# rat17-18.net
KiCad netlist of a schematic drawn in EAGLE
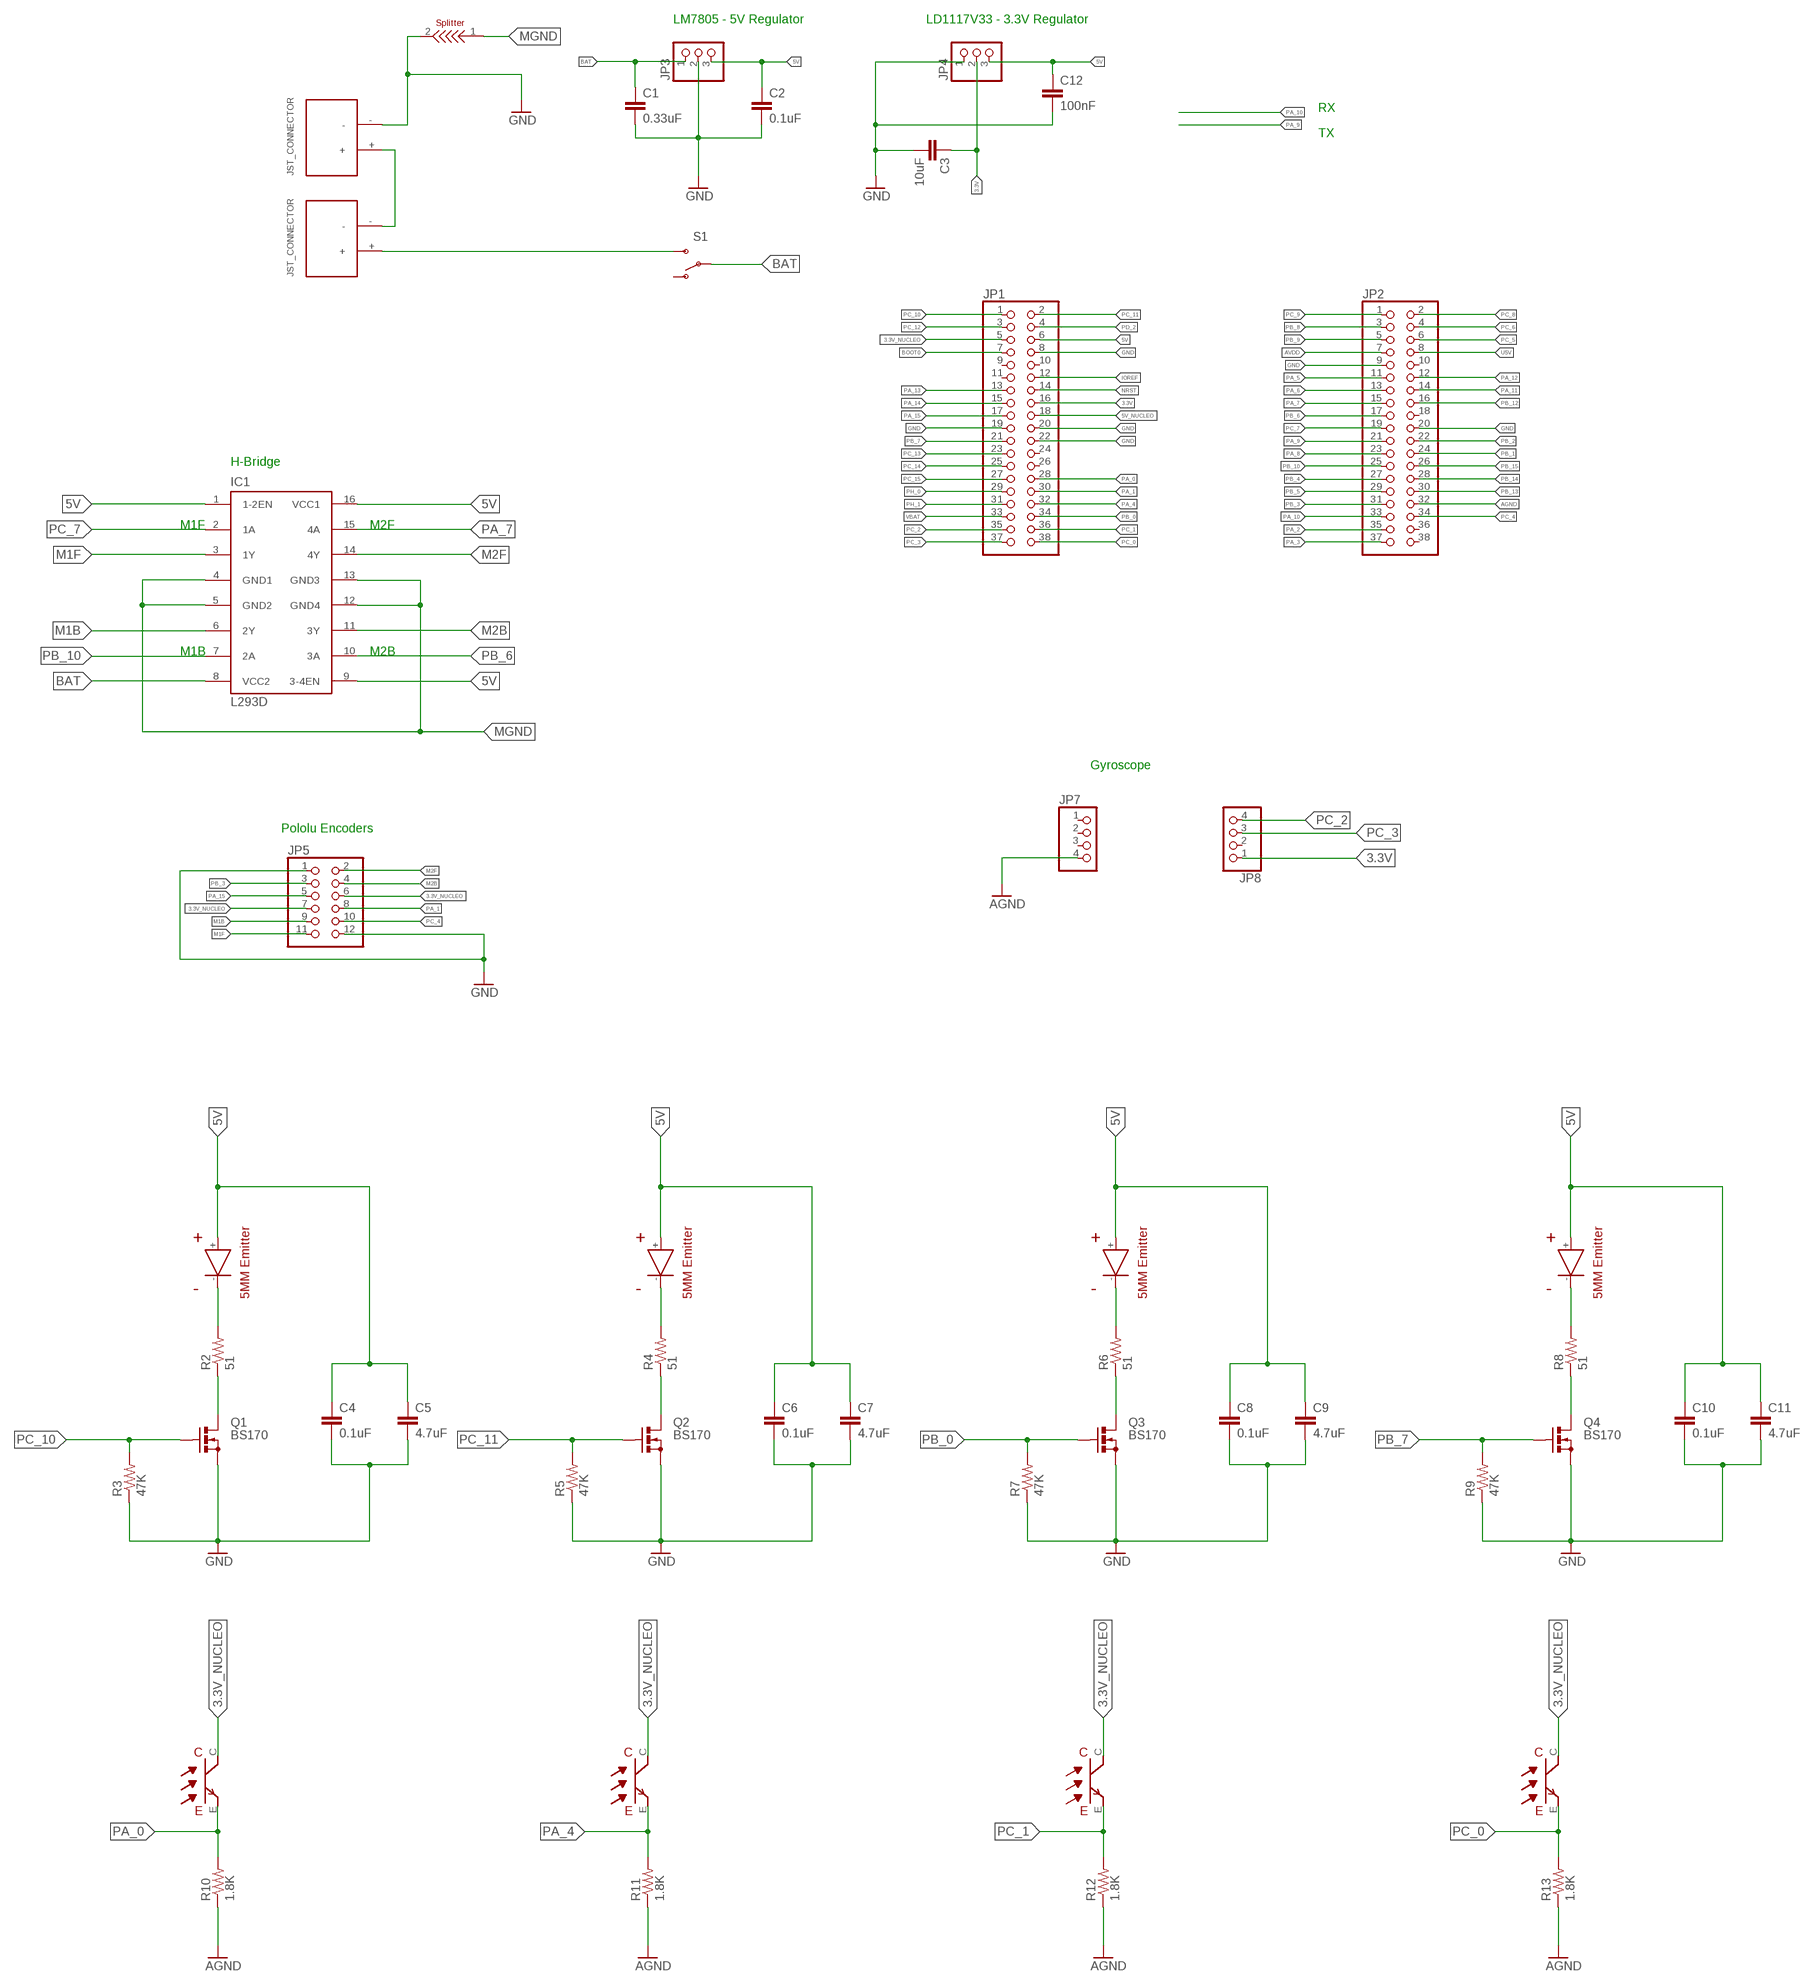
[diagram p0: schematic, sheet 1]

(export (version "E")
  (design (tool "Eeschema 10.0.6"))
  (components
    (comp (ref "C1")
      (value "0.33uF")
      (footprint "eagle-import:AXIAL-5MM")
      (libsource (lib "eagle-import") (part "CAP_"))
    )
    (comp (ref "C2")
      (value "0.1uF")
      (footprint "eagle-import:AXIAL-5MM")
      (libsource (lib "eagle-import") (part "CAP_"))
    )
    (comp (ref "C3")
      (value "10uF")
      (footprint "eagle-import:AXIAL-5MM")
      (libsource (lib "eagle-import") (part "CAP_"))
    )
    (comp (ref "C4")
      (value "0.1uF")
      (footprint "eagle-import:AXIAL-5MM")
      (libsource (lib "eagle-import") (part "CAP_"))
    )
    (comp (ref "C5")
      (value "4.7uF")
      (footprint "eagle-import:AXIAL-5MM")
      (libsource (lib "eagle-import") (part "CAP_"))
    )
    (comp (ref "C6")
      (value "0.1uF")
      (footprint "eagle-import:AXIAL-5MM")
      (libsource (lib "eagle-import") (part "CAP_"))
    )
    (comp (ref "C7")
      (value "4.7uF")
      (footprint "eagle-import:AXIAL-5MM")
      (libsource (lib "eagle-import") (part "CAP_"))
    )
    (comp (ref "C8")
      (value "0.1uF")
      (footprint "eagle-import:AXIAL-5MM")
      (libsource (lib "eagle-import") (part "CAP_"))
    )
    (comp (ref "C9")
      (value "4.7uF")
      (footprint "eagle-import:AXIAL-5MM")
      (libsource (lib "eagle-import") (part "CAP_"))
    )
    (comp (ref "C10")
      (value "0.1uF")
      (footprint "eagle-import:AXIAL-5MM")
      (libsource (lib "eagle-import") (part "CAP_"))
    )
    (comp (ref "C11")
      (value "4.7uF")
      (footprint "eagle-import:AXIAL-5MM")
      (libsource (lib "eagle-import") (part "CAP_"))
    )
    (comp (ref "C12")
      (value "100nF")
      (footprint "eagle-import:AXIAL-5MM")
      (libsource (lib "eagle-import") (part "CAP_"))
    )
    (comp (ref "IC1")
      (value "L293D")
      (footprint "eagle-import:DIL16")
      (libsource (lib "eagle-import") (part "L293D"))
    )
    (comp (ref "JP1")
      (value "PINHD-2X19")
      (footprint "eagle-import:2X19")
      (libsource (lib "eagle-import") (part "PINHD-2X19"))
    )
    (comp (ref "JP2")
      (value "PINHD-2X19")
      (footprint "eagle-import:2X19")
      (libsource (lib "eagle-import") (part "PINHD-2X19"))
    )
    (comp (ref "JP3")
      (value "PINHD-1X3")
      (footprint "eagle-import:1X03")
      (libsource (lib "eagle-import") (part "PINHD-1X3"))
    )
    (comp (ref "JP4")
      (value "PINHD-1X3")
      (footprint "eagle-import:1X03")
      (libsource (lib "eagle-import") (part "PINHD-1X3"))
    )
    (comp (ref "JP5")
      (value "PINHD-2X6")
      (footprint "eagle-import:2X06")
      (libsource (lib "eagle-import") (part "PINHD-2X6"))
    )
    (comp (ref "JP7")
      (value "PINHD-1X4")
      (footprint "eagle-import:1X04")
      (libsource (lib "eagle-import") (part "PINHD-1X4"))
    )
    (comp (ref "JP8")
      (value "PINHD-1X4")
      (footprint "eagle-import:1X04")
      (libsource (lib "eagle-import") (part "PINHD-1X4"))
    )
    (comp (ref "Q1")
      (value "BS170")
      (footprint "eagle-import:SOT54E")
      (libsource (lib "eagle-import") (part "BS170"))
    )
    (comp (ref "Q2")
      (value "BS170")
      (footprint "eagle-import:SOT54E")
      (libsource (lib "eagle-import") (part "BS170"))
    )
    (comp (ref "Q3")
      (value "BS170")
      (footprint "eagle-import:SOT54E")
      (libsource (lib "eagle-import") (part "BS170"))
    )
    (comp (ref "Q4")
      (value "BS170")
      (footprint "eagle-import:SOT54E")
      (libsource (lib "eagle-import") (part "BS170"))
    )
    (comp (ref "R2")
      (value "51")
      (footprint "eagle-import:AXIAL-0.3")
      (libsource (lib "eagle-import") (part "RESISTORAXIAL-0.3"))
    )
    (comp (ref "R3")
      (value "47K")
      (footprint "eagle-import:AXIAL-0.3")
      (libsource (lib "eagle-import") (part "RESISTORAXIAL-0.3"))
    )
    (comp (ref "R4")
      (value "51")
      (footprint "eagle-import:AXIAL-0.3")
      (libsource (lib "eagle-import") (part "RESISTORAXIAL-0.3"))
    )
    (comp (ref "R5")
      (value "47K")
      (footprint "eagle-import:AXIAL-0.3")
      (libsource (lib "eagle-import") (part "RESISTORAXIAL-0.3"))
    )
    (comp (ref "R6")
      (value "51")
      (footprint "eagle-import:AXIAL-0.3")
      (libsource (lib "eagle-import") (part "RESISTORAXIAL-0.3"))
    )
    (comp (ref "R7")
      (value "47K")
      (footprint "eagle-import:AXIAL-0.3")
      (libsource (lib "eagle-import") (part "RESISTORAXIAL-0.3"))
    )
    (comp (ref "R8")
      (value "51")
      (footprint "eagle-import:AXIAL-0.3")
      (libsource (lib "eagle-import") (part "RESISTORAXIAL-0.3"))
    )
    (comp (ref "R9")
      (value "47K")
      (footprint "eagle-import:AXIAL-0.3")
      (libsource (lib "eagle-import") (part "RESISTORAXIAL-0.3"))
    )
    (comp (ref "R10")
      (value "1.8K")
      (footprint "eagle-import:AXIAL-0.3")
      (libsource (lib "eagle-import") (part "RESISTORAXIAL-0.3"))
    )
    (comp (ref "R11")
      (value "1.8K")
      (footprint "eagle-import:AXIAL-0.3")
      (libsource (lib "eagle-import") (part "RESISTORAXIAL-0.3"))
    )
    (comp (ref "R12")
      (value "1.8K")
      (footprint "eagle-import:AXIAL-0.3")
      (libsource (lib "eagle-import") (part "RESISTORAXIAL-0.3"))
    )
    (comp (ref "R13")
      (value "1.8K")
      (footprint "eagle-import:AXIAL-0.3")
      (libsource (lib "eagle-import") (part "RESISTORAXIAL-0.3"))
    )
    (comp (ref "S1")
      (value "SWITCH-SPSTPTH")
      (footprint "eagle-import:SWITCH-SPDT")
      (libsource (lib "eagle-import") (part "SWITCH-SPSTPTH"))
    )
    (comp (ref "U$1")
      (value "JST_CONNECTOR_FEMALE")
      (footprint "eagle-import:JST_CONNECTOR_FEMALE")
      (libsource (lib "eagle-import") (part "JST_CONNECTOR_FEMALE"))
    )
    (comp (ref "U$2")
      (value "JST_CONNECTOR_FEMALE")
      (footprint "eagle-import:JST_CONNECTOR_FEMALE")
      (libsource (lib "eagle-import") (part "JST_CONNECTOR_FEMALE"))
    )
    (comp (ref "U$3")
      (value "SPLITTER")
      (footprint "eagle-import:SPLITTER")
      (libsource (lib "eagle-import") (part "SPLITTER"))
    )
    (comp (ref "U$4")
      (value "RECEIVER")
      (footprint "eagle-import:RECEIVER")
      (libsource (lib "eagle-import") (part "RECEIVER"))
    )
    (comp (ref "U$5")
      (value "EMITTER")
      (footprint "eagle-import:EMITTER")
      (libsource (lib "eagle-import") (part "EMITTER"))
    )
    (comp (ref "U$6")
      (value "EMITTER")
      (footprint "eagle-import:EMITTER")
      (libsource (lib "eagle-import") (part "EMITTER"))
    )
    (comp (ref "U$7")
      (value "EMITTER")
      (footprint "eagle-import:EMITTER")
      (libsource (lib "eagle-import") (part "EMITTER"))
    )
    (comp (ref "U$8")
      (value "EMITTER")
      (footprint "eagle-import:EMITTER")
      (libsource (lib "eagle-import") (part "EMITTER"))
    )
    (comp (ref "U$15")
      (value "RECEIVER")
      (footprint "eagle-import:RECEIVER")
      (libsource (lib "eagle-import") (part "RECEIVER"))
    )
    (comp (ref "U$18")
      (value "RECEIVER")
      (footprint "eagle-import:RECEIVER")
      (libsource (lib "eagle-import") (part "RECEIVER"))
    )
    (comp (ref "U$19")
      (value "RECEIVER")
      (footprint "eagle-import:RECEIVER")
      (libsource (lib "eagle-import") (part "RECEIVER"))
    )
  )
  (nets
    (net (code "1") (name "3.3V") (class "Default")
      (node (ref "C3") (pin "P$1") (pinfunction "1_P$1") (pintype "passive"))
      (node (ref "JP1") (pin "16") (pinfunction "16_16") (pintype "passive"))
      (node (ref "JP4") (pin "2") (pinfunction "2_2") (pintype "passive"))
      (node (ref "JP8") (pin "1") (pinfunction "1_1") (pintype "passive"))
    )
    (net (code "2") (name "3.3V_NUCLEO") (class "Default")
      (node (ref "JP1") (pin "5") (pinfunction "5_5") (pintype "passive"))
      (node (ref "JP5") (pin "6") (pinfunction "6_6") (pintype "passive"))
      (node (ref "JP5") (pin "7") (pinfunction "7_7") (pintype "passive"))
      (node (ref "U$15") (pin "C") (pinfunction "C_C") (pintype "bidirectional"))
      (node (ref "U$18") (pin "C") (pinfunction "C_C") (pintype "bidirectional"))
      (node (ref "U$19") (pin "C") (pinfunction "C_C") (pintype "bidirectional"))
      (node (ref "U$4") (pin "C") (pinfunction "C_C") (pintype "bidirectional"))
    )
    (net (code "3") (name "5V") (class "Default")
      (node (ref "C10") (pin "P$1") (pinfunction "1_P$1") (pintype "passive"))
      (node (ref "C11") (pin "P$1") (pinfunction "1_P$1") (pintype "passive"))
      (node (ref "C12") (pin "P$1") (pinfunction "1_P$1") (pintype "passive"))
      (node (ref "C2") (pin "P$1") (pinfunction "1_P$1") (pintype "passive"))
      (node (ref "C4") (pin "P$1") (pinfunction "1_P$1") (pintype "passive"))
      (node (ref "C5") (pin "P$1") (pinfunction "1_P$1") (pintype "passive"))
      (node (ref "C6") (pin "P$1") (pinfunction "1_P$1") (pintype "passive"))
      (node (ref "C7") (pin "P$1") (pinfunction "1_P$1") (pintype "passive"))
      (node (ref "C8") (pin "P$1") (pinfunction "1_P$1") (pintype "passive"))
      (node (ref "C9") (pin "P$1") (pinfunction "1_P$1") (pintype "passive"))
      (node (ref "IC1") (pin "1") (pinfunction "1-2EN_1") (pintype "input"))
      (node (ref "IC1") (pin "16") (pinfunction "VCC1_16") (pintype "power_in"))
      (node (ref "IC1") (pin "9") (pinfunction "3-4EN_9") (pintype "input"))
      (node (ref "JP1") (pin "6") (pinfunction "6_6") (pintype "passive"))
      (node (ref "JP3") (pin "3") (pinfunction "3_3") (pintype "passive"))
      (node (ref "JP4") (pin "3") (pinfunction "3_3") (pintype "passive"))
      (node (ref "U$5") (pin "+") (pinfunction "+_+") (pintype "bidirectional"))
      (node (ref "U$6") (pin "+") (pinfunction "+_+") (pintype "bidirectional"))
      (node (ref "U$7") (pin "+") (pinfunction "+_+") (pintype "bidirectional"))
      (node (ref "U$8") (pin "+") (pinfunction "+_+") (pintype "bidirectional"))
    )
    (net (code "4") (name "5V_NUCLEO") (class "Default")
      (node (ref "JP1") (pin "18") (pinfunction "18_18") (pintype "passive"))
    )
    (net (code "5") (name "AGND") (class "Default")
      (node (ref "JP2") (pin "32") (pinfunction "32_32") (pintype "passive"))
      (node (ref "JP7") (pin "4") (pinfunction "4_4") (pintype "passive"))
      (node (ref "R10") (pin "P$1") (pinfunction "1_P$1") (pintype "passive"))
      (node (ref "R11") (pin "P$1") (pinfunction "1_P$1") (pintype "passive"))
      (node (ref "R12") (pin "P$1") (pinfunction "1_P$1") (pintype "passive"))
      (node (ref "R13") (pin "P$1") (pinfunction "1_P$1") (pintype "passive"))
    )
    (net (code "6") (name "AVDD") (class "Default")
      (node (ref "JP2") (pin "7") (pinfunction "7_7") (pintype "passive"))
    )
    (net (code "7") (name "BAT") (class "Default")
      (node (ref "C1") (pin "P$1") (pinfunction "1_P$1") (pintype "passive"))
      (node (ref "IC1") (pin "8") (pinfunction "VCC2_8") (pintype "power_in"))
      (node (ref "JP3") (pin "1") (pinfunction "1_1") (pintype "passive"))
      (node (ref "S1") (pin "2") (pinfunction "P_2") (pintype "passive"))
    )
    (net (code "8") (name "BOOT0") (class "Default")
      (node (ref "JP1") (pin "7") (pinfunction "7_7") (pintype "passive"))
    )
    (net (code "9") (name "GND") (class "Default")
      (node (ref "C1") (pin "P$2") (pinfunction "2_P$2") (pintype "passive"))
      (node (ref "C10") (pin "P$2") (pinfunction "2_P$2") (pintype "passive"))
      (node (ref "C11") (pin "P$2") (pinfunction "2_P$2") (pintype "passive"))
      (node (ref "C12") (pin "P$2") (pinfunction "2_P$2") (pintype "passive"))
      (node (ref "C2") (pin "P$2") (pinfunction "2_P$2") (pintype "passive"))
      (node (ref "C3") (pin "P$2") (pinfunction "2_P$2") (pintype "passive"))
      (node (ref "C4") (pin "P$2") (pinfunction "2_P$2") (pintype "passive"))
      (node (ref "C5") (pin "P$2") (pinfunction "2_P$2") (pintype "passive"))
      (node (ref "C6") (pin "P$2") (pinfunction "2_P$2") (pintype "passive"))
      (node (ref "C7") (pin "P$2") (pinfunction "2_P$2") (pintype "passive"))
      (node (ref "C8") (pin "P$2") (pinfunction "2_P$2") (pintype "passive"))
      (node (ref "C9") (pin "P$2") (pinfunction "2_P$2") (pintype "passive"))
      (node (ref "JP1") (pin "19") (pinfunction "19_19") (pintype "passive"))
      (node (ref "JP1") (pin "20") (pinfunction "20_20") (pintype "passive"))
      (node (ref "JP1") (pin "22") (pinfunction "22_22") (pintype "passive"))
      (node (ref "JP1") (pin "8") (pinfunction "8_8") (pintype "passive"))
      (node (ref "JP2") (pin "20") (pinfunction "20_20") (pintype "passive"))
      (node (ref "JP2") (pin "9") (pinfunction "9_9") (pintype "passive"))
      (node (ref "JP3") (pin "2") (pinfunction "2_2") (pintype "passive"))
      (node (ref "JP4") (pin "1") (pinfunction "1_1") (pintype "passive"))
      (node (ref "JP5") (pin "1") (pinfunction "1_1") (pintype "passive"))
      (node (ref "JP5") (pin "12") (pinfunction "12_12") (pintype "passive"))
      (node (ref "Q1") (pin "S") (pinfunction "S_S") (pintype "passive"))
      (node (ref "Q2") (pin "S") (pinfunction "S_S") (pintype "passive"))
      (node (ref "Q3") (pin "S") (pinfunction "S_S") (pintype "passive"))
      (node (ref "Q4") (pin "S") (pinfunction "S_S") (pintype "passive"))
      (node (ref "R3") (pin "P$1") (pinfunction "1_P$1") (pintype "passive"))
      (node (ref "R5") (pin "P$1") (pinfunction "1_P$1") (pintype "passive"))
      (node (ref "R7") (pin "P$1") (pinfunction "1_P$1") (pintype "passive"))
      (node (ref "R9") (pin "P$1") (pinfunction "1_P$1") (pintype "passive"))
      (node (ref "U$1") (pin "-") (pinfunction "-_-") (pintype "bidirectional"))
      (node (ref "U$3") (pin "2") (pinfunction "2_2") (pintype "bidirectional"))
    )
    (net (code "10") (name "IOREF") (class "Default")
      (node (ref "JP1") (pin "12") (pinfunction "12_12") (pintype "passive"))
    )
    (net (code "11") (name "M1B") (class "Default")
      (node (ref "IC1") (pin "6") (pinfunction "2Y_6") (pintype "output"))
      (node (ref "JP5") (pin "9") (pinfunction "9_9") (pintype "passive"))
    )
    (net (code "12") (name "M1F") (class "Default")
      (node (ref "IC1") (pin "3") (pinfunction "1Y_3") (pintype "output"))
      (node (ref "JP5") (pin "11") (pinfunction "11_11") (pintype "passive"))
    )
    (net (code "13") (name "M2B") (class "Default")
      (node (ref "IC1") (pin "11") (pinfunction "3Y_11") (pintype "output"))
      (node (ref "JP5") (pin "4") (pinfunction "4_4") (pintype "passive"))
    )
    (net (code "14") (name "M2F") (class "Default")
      (node (ref "IC1") (pin "14") (pinfunction "4Y_14") (pintype "output"))
      (node (ref "JP5") (pin "2") (pinfunction "2_2") (pintype "passive"))
    )
    (net (code "15") (name "MGND") (class "Default")
      (node (ref "IC1") (pin "12") (pinfunction "GND4_12") (pintype "power_in"))
      (node (ref "IC1") (pin "13") (pinfunction "GND3_13") (pintype "power_in"))
      (node (ref "IC1") (pin "4") (pinfunction "GND1_4") (pintype "power_in"))
      (node (ref "IC1") (pin "5") (pinfunction "GND2_5") (pintype "power_in"))
      (node (ref "U$3") (pin "1") (pinfunction "1_1") (pintype "bidirectional"))
    )
    (net (code "16") (name "NRST") (class "Default")
      (node (ref "JP1") (pin "14") (pinfunction "14_14") (pintype "passive"))
    )
    (net (code "17") (name "Net-(R2-1)") (class "Default")
      (node (ref "Q1") (pin "D") (pinfunction "D_D") (pintype "passive"))
      (node (ref "R2") (pin "P$1") (pinfunction "1_P$1") (pintype "passive"))
    )
    (net (code "18") (name "Net-(R2-2)") (class "Default")
      (node (ref "R2") (pin "P$2") (pinfunction "2_P$2") (pintype "passive"))
      (node (ref "U$5") (pin "-") (pinfunction "-_-") (pintype "bidirectional"))
    )
    (net (code "19") (name "Net-(R4-1)") (class "Default")
      (node (ref "Q2") (pin "D") (pinfunction "D_D") (pintype "passive"))
      (node (ref "R4") (pin "P$1") (pinfunction "1_P$1") (pintype "passive"))
    )
    (net (code "20") (name "Net-(R4-2)") (class "Default")
      (node (ref "R4") (pin "P$2") (pinfunction "2_P$2") (pintype "passive"))
      (node (ref "U$6") (pin "-") (pinfunction "-_-") (pintype "bidirectional"))
    )
    (net (code "21") (name "Net-(R6-1)") (class "Default")
      (node (ref "Q3") (pin "D") (pinfunction "D_D") (pintype "passive"))
      (node (ref "R6") (pin "P$1") (pinfunction "1_P$1") (pintype "passive"))
    )
    (net (code "22") (name "Net-(R6-2)") (class "Default")
      (node (ref "R6") (pin "P$2") (pinfunction "2_P$2") (pintype "passive"))
      (node (ref "U$7") (pin "-") (pinfunction "-_-") (pintype "bidirectional"))
    )
    (net (code "23") (name "Net-(R8-1)") (class "Default")
      (node (ref "Q4") (pin "D") (pinfunction "D_D") (pintype "passive"))
      (node (ref "R8") (pin "P$1") (pinfunction "1_P$1") (pintype "passive"))
    )
    (net (code "24") (name "Net-(R8-2)") (class "Default")
      (node (ref "R8") (pin "P$2") (pinfunction "2_P$2") (pintype "passive"))
      (node (ref "U$8") (pin "-") (pinfunction "-_-") (pintype "bidirectional"))
    )
    (net (code "25") (name "Net-(S1-S)") (class "Default")
      (node (ref "S1") (pin "3") (pinfunction "S_3") (pintype "passive"))
      (node (ref "U$2") (pin "+") (pinfunction "+_+") (pintype "bidirectional"))
    )
    (net (code "26") (name "Net-(U$1-Pad+)") (class "Default")
      (node (ref "U$1") (pin "+") (pinfunction "+_+") (pintype "bidirectional"))
      (node (ref "U$2") (pin "-") (pinfunction "-_-") (pintype "bidirectional"))
    )
    (net (code "27") (name "PA_0") (class "Default")
      (node (ref "JP1") (pin "28") (pinfunction "28_28") (pintype "passive"))
      (node (ref "R10") (pin "P$2") (pinfunction "2_P$2") (pintype "passive"))
      (node (ref "U$19") (pin "E") (pinfunction "E_E") (pintype "bidirectional"))
    )
    (net (code "28") (name "PA_1") (class "Default")
      (node (ref "JP1") (pin "30") (pinfunction "30_30") (pintype "passive"))
      (node (ref "JP5") (pin "8") (pinfunction "8_8") (pintype "passive"))
    )
    (net (code "29") (name "PA_2") (class "Default")
      (node (ref "JP2") (pin "35") (pinfunction "35_35") (pintype "passive"))
    )
    (net (code "30") (name "PA_3") (class "Default")
      (node (ref "JP2") (pin "37") (pinfunction "37_37") (pintype "passive"))
    )
    (net (code "31") (name "PA_4") (class "Default")
      (node (ref "JP1") (pin "32") (pinfunction "32_32") (pintype "passive"))
      (node (ref "R11") (pin "P$2") (pinfunction "2_P$2") (pintype "passive"))
      (node (ref "U$18") (pin "E") (pinfunction "E_E") (pintype "bidirectional"))
    )
    (net (code "32") (name "PA_5") (class "Default")
      (node (ref "JP2") (pin "11") (pinfunction "11_11") (pintype "passive"))
    )
    (net (code "33") (name "PA_6") (class "Default")
      (node (ref "JP2") (pin "13") (pinfunction "13_13") (pintype "passive"))
    )
    (net (code "34") (name "PA_7") (class "Default")
      (node (ref "IC1") (pin "15") (pinfunction "4A_15") (pintype "input"))
      (node (ref "JP2") (pin "15") (pinfunction "15_15") (pintype "passive"))
    )
    (net (code "35") (name "PA_8") (class "Default")
      (node (ref "JP2") (pin "23") (pinfunction "23_23") (pintype "passive"))
    )
    (net (code "36") (name "PA_9") (class "Default")
      (node (ref "JP2") (pin "21") (pinfunction "21_21") (pintype "passive"))
    )
    (net (code "37") (name "PA_10") (class "Default")
      (node (ref "JP2") (pin "33") (pinfunction "33_33") (pintype "passive"))
    )
    (net (code "38") (name "PA_11") (class "Default")
      (node (ref "JP2") (pin "14") (pinfunction "14_14") (pintype "passive"))
    )
    (net (code "39") (name "PA_12") (class "Default")
      (node (ref "JP2") (pin "12") (pinfunction "12_12") (pintype "passive"))
    )
    (net (code "40") (name "PA_13") (class "Default")
      (node (ref "JP1") (pin "13") (pinfunction "13_13") (pintype "passive"))
    )
    (net (code "41") (name "PA_14") (class "Default")
      (node (ref "JP1") (pin "15") (pinfunction "15_15") (pintype "passive"))
    )
    (net (code "42") (name "PA_15") (class "Default")
      (node (ref "JP1") (pin "17") (pinfunction "17_17") (pintype "passive"))
      (node (ref "JP5") (pin "5") (pinfunction "5_5") (pintype "passive"))
    )
    (net (code "43") (name "PB_0") (class "Default")
      (node (ref "JP1") (pin "34") (pinfunction "34_34") (pintype "passive"))
      (node (ref "Q3") (pin "G") (pinfunction "G_G") (pintype "passive"))
      (node (ref "R7") (pin "P$2") (pinfunction "2_P$2") (pintype "passive"))
    )
    (net (code "44") (name "PB_1") (class "Default")
      (node (ref "JP2") (pin "24") (pinfunction "24_24") (pintype "passive"))
    )
    (net (code "45") (name "PB_2") (class "Default")
      (node (ref "JP2") (pin "22") (pinfunction "22_22") (pintype "passive"))
    )
    (net (code "46") (name "PB_3") (class "Default")
      (node (ref "JP2") (pin "31") (pinfunction "31_31") (pintype "passive"))
      (node (ref "JP5") (pin "3") (pinfunction "3_3") (pintype "passive"))
    )
    (net (code "47") (name "PB_4") (class "Default")
      (node (ref "JP2") (pin "27") (pinfunction "27_27") (pintype "passive"))
    )
    (net (code "48") (name "PB_5") (class "Default")
      (node (ref "JP2") (pin "29") (pinfunction "29_29") (pintype "passive"))
    )
    (net (code "49") (name "PB_6") (class "Default")
      (node (ref "IC1") (pin "10") (pinfunction "3A_10") (pintype "input"))
      (node (ref "JP2") (pin "17") (pinfunction "17_17") (pintype "passive"))
    )
    (net (code "50") (name "PB_7") (class "Default")
      (node (ref "JP1") (pin "21") (pinfunction "21_21") (pintype "passive"))
      (node (ref "Q4") (pin "G") (pinfunction "G_G") (pintype "passive"))
      (node (ref "R9") (pin "P$2") (pinfunction "2_P$2") (pintype "passive"))
    )
    (net (code "51") (name "PB_8") (class "Default")
      (node (ref "JP2") (pin "3") (pinfunction "3_3") (pintype "passive"))
    )
    (net (code "52") (name "PB_9") (class "Default")
      (node (ref "JP2") (pin "5") (pinfunction "5_5") (pintype "passive"))
    )
    (net (code "53") (name "PB_10") (class "Default")
      (node (ref "IC1") (pin "7") (pinfunction "2A_7") (pintype "input"))
      (node (ref "JP2") (pin "25") (pinfunction "25_25") (pintype "passive"))
    )
    (net (code "54") (name "PB_12") (class "Default")
      (node (ref "JP2") (pin "16") (pinfunction "16_16") (pintype "passive"))
    )
    (net (code "55") (name "PB_13") (class "Default")
      (node (ref "JP2") (pin "30") (pinfunction "30_30") (pintype "passive"))
    )
    (net (code "56") (name "PB_14") (class "Default")
      (node (ref "JP2") (pin "28") (pinfunction "28_28") (pintype "passive"))
    )
    (net (code "57") (name "PB_15") (class "Default")
      (node (ref "JP2") (pin "26") (pinfunction "26_26") (pintype "passive"))
    )
    (net (code "58") (name "PC_0") (class "Default")
      (node (ref "JP1") (pin "38") (pinfunction "38_38") (pintype "passive"))
      (node (ref "R13") (pin "P$2") (pinfunction "2_P$2") (pintype "passive"))
      (node (ref "U$4") (pin "E") (pinfunction "E_E") (pintype "bidirectional"))
    )
    (net (code "59") (name "PC_1") (class "Default")
      (node (ref "JP1") (pin "36") (pinfunction "36_36") (pintype "passive"))
      (node (ref "R12") (pin "P$2") (pinfunction "2_P$2") (pintype "passive"))
      (node (ref "U$15") (pin "E") (pinfunction "E_E") (pintype "bidirectional"))
    )
    (net (code "60") (name "PC_2") (class "Default")
      (node (ref "JP1") (pin "35") (pinfunction "35_35") (pintype "passive"))
      (node (ref "JP8") (pin "4") (pinfunction "4_4") (pintype "passive"))
    )
    (net (code "61") (name "PC_3") (class "Default")
      (node (ref "JP1") (pin "37") (pinfunction "37_37") (pintype "passive"))
      (node (ref "JP8") (pin "3") (pinfunction "3_3") (pintype "passive"))
    )
    (net (code "62") (name "PC_4") (class "Default")
      (node (ref "JP2") (pin "34") (pinfunction "34_34") (pintype "passive"))
      (node (ref "JP5") (pin "10") (pinfunction "10_10") (pintype "passive"))
    )
    (net (code "63") (name "PC_5") (class "Default")
      (node (ref "JP2") (pin "6") (pinfunction "6_6") (pintype "passive"))
    )
    (net (code "64") (name "PC_6") (class "Default")
      (node (ref "JP2") (pin "4") (pinfunction "4_4") (pintype "passive"))
    )
    (net (code "65") (name "PC_7") (class "Default")
      (node (ref "IC1") (pin "2") (pinfunction "1A_2") (pintype "input"))
      (node (ref "JP2") (pin "19") (pinfunction "19_19") (pintype "passive"))
    )
    (net (code "66") (name "PC_8") (class "Default")
      (node (ref "JP2") (pin "2") (pinfunction "2_2") (pintype "passive"))
    )
    (net (code "67") (name "PC_9") (class "Default")
      (node (ref "JP2") (pin "1") (pinfunction "1_1") (pintype "passive"))
    )
    (net (code "68") (name "PC_10") (class "Default")
      (node (ref "JP1") (pin "1") (pinfunction "1_1") (pintype "passive"))
      (node (ref "Q1") (pin "G") (pinfunction "G_G") (pintype "passive"))
      (node (ref "R3") (pin "P$2") (pinfunction "2_P$2") (pintype "passive"))
    )
    (net (code "69") (name "PC_11") (class "Default")
      (node (ref "JP1") (pin "2") (pinfunction "2_2") (pintype "passive"))
      (node (ref "Q2") (pin "G") (pinfunction "G_G") (pintype "passive"))
      (node (ref "R5") (pin "P$2") (pinfunction "2_P$2") (pintype "passive"))
    )
    (net (code "70") (name "PC_12") (class "Default")
      (node (ref "JP1") (pin "3") (pinfunction "3_3") (pintype "passive"))
    )
    (net (code "71") (name "PC_13") (class "Default")
      (node (ref "JP1") (pin "23") (pinfunction "23_23") (pintype "passive"))
    )
    (net (code "72") (name "PC_14") (class "Default")
      (node (ref "JP1") (pin "25") (pinfunction "25_25") (pintype "passive"))
    )
    (net (code "73") (name "PC_15") (class "Default")
      (node (ref "JP1") (pin "27") (pinfunction "27_27") (pintype "passive"))
    )
    (net (code "74") (name "PD_2") (class "Default")
      (node (ref "JP1") (pin "4") (pinfunction "4_4") (pintype "passive"))
    )
    (net (code "75") (name "PH_0") (class "Default")
      (node (ref "JP1") (pin "29") (pinfunction "29_29") (pintype "passive"))
    )
    (net (code "76") (name "PH_1") (class "Default")
      (node (ref "JP1") (pin "31") (pinfunction "31_31") (pintype "passive"))
    )
    (net (code "77") (name "U5V") (class "Default")
      (node (ref "JP2") (pin "8") (pinfunction "8_8") (pintype "passive"))
    )
    (net (code "78") (name "VBAT") (class "Default")
      (node (ref "JP1") (pin "33") (pinfunction "33_33") (pintype "passive"))
    )
    (net (code "79") (name "unconnected-(JP1-Pad9)") (class "Default")
      (node (ref "JP1") (pin "9") (pinfunction "9_9") (pintype "passive"))
    )
    (net (code "80") (name "unconnected-(JP1-Pad10)") (class "Default")
      (node (ref "JP1") (pin "10") (pinfunction "10_10") (pintype "passive"))
    )
    (net (code "81") (name "unconnected-(JP1-Pad11)") (class "Default")
      (node (ref "JP1") (pin "11") (pinfunction "11_11") (pintype "passive"))
    )
    (net (code "82") (name "unconnected-(JP1-Pad24)") (class "Default")
      (node (ref "JP1") (pin "24") (pinfunction "24_24") (pintype "passive"))
    )
    (net (code "83") (name "unconnected-(JP1-Pad26)") (class "Default")
      (node (ref "JP1") (pin "26") (pinfunction "26_26") (pintype "passive"))
    )
    (net (code "84") (name "unconnected-(JP2-Pad10)") (class "Default")
      (node (ref "JP2") (pin "10") (pinfunction "10_10") (pintype "passive"))
    )
    (net (code "85") (name "unconnected-(JP2-Pad18)") (class "Default")
      (node (ref "JP2") (pin "18") (pinfunction "18_18") (pintype "passive"))
    )
    (net (code "86") (name "unconnected-(JP2-Pad36)") (class "Default")
      (node (ref "JP2") (pin "36") (pinfunction "36_36") (pintype "passive"))
    )
    (net (code "87") (name "unconnected-(JP2-Pad38)") (class "Default")
      (node (ref "JP2") (pin "38") (pinfunction "38_38") (pintype "passive"))
    )
    (net (code "88") (name "unconnected-(JP7-Pad1)") (class "Default")
      (node (ref "JP7") (pin "1") (pinfunction "1_1") (pintype "passive"))
    )
    (net (code "89") (name "unconnected-(JP7-Pad2)") (class "Default")
      (node (ref "JP7") (pin "2") (pinfunction "2_2") (pintype "passive"))
    )
    (net (code "90") (name "unconnected-(JP7-Pad3)") (class "Default")
      (node (ref "JP7") (pin "3") (pinfunction "3_3") (pintype "passive"))
    )
    (net (code "91") (name "unconnected-(JP8-Pad2)") (class "Default")
      (node (ref "JP8") (pin "2") (pinfunction "2_2") (pintype "passive"))
    )
    (net (code "92") (name "unconnected-(S1-O-Pad1)") (class "Default")
      (node (ref "S1") (pin "1") (pinfunction "O_1") (pintype "passive"))
    )
  )
)
